# stm32103c8t6-v7.net
KiCad netlist of a schematic drawn in EAGLE
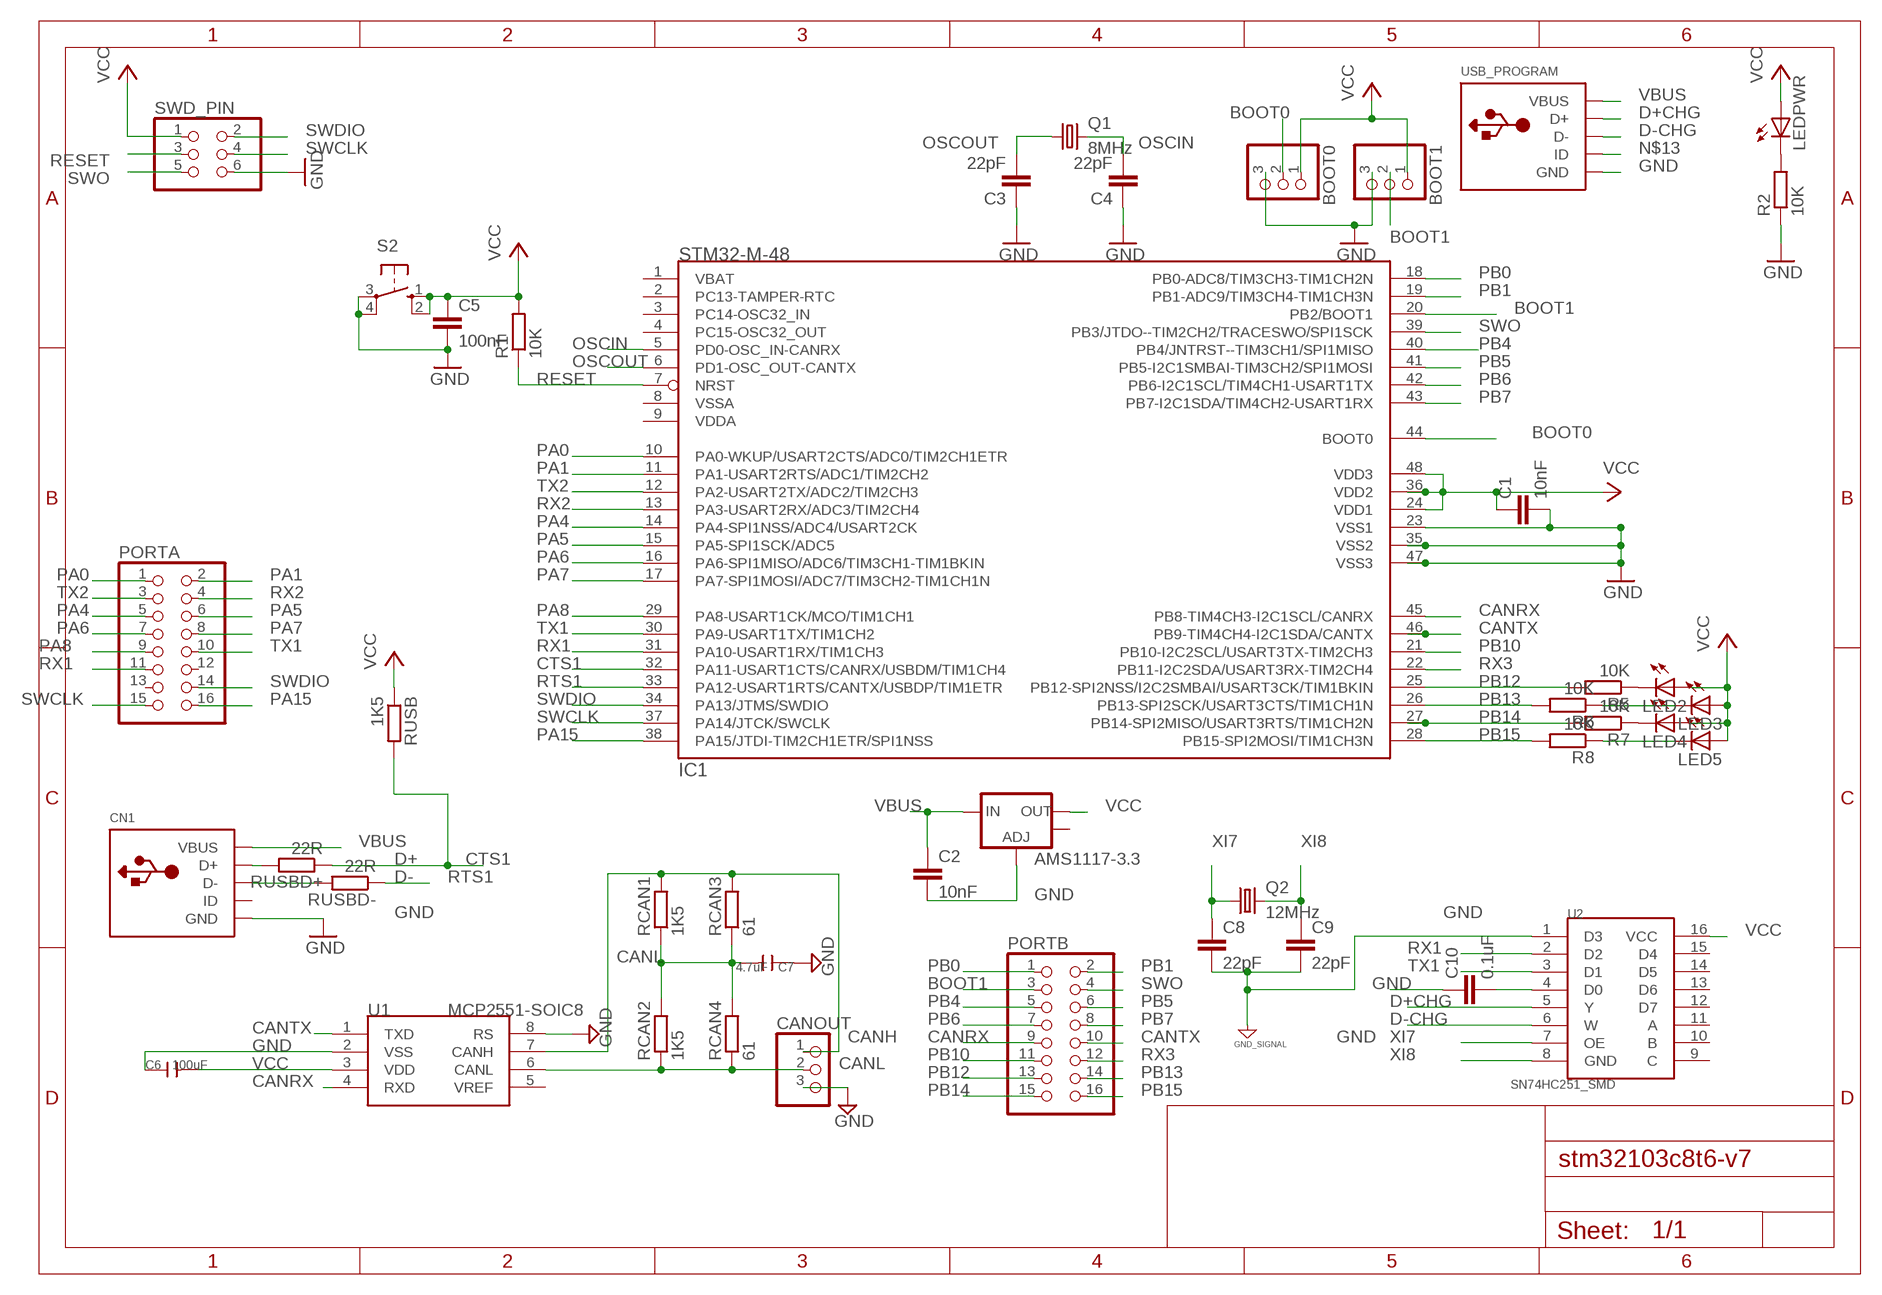
[diagram p0: schematic, sheet 1]

(export (version "E")
  (design (tool "Eeschema 10.0.6"))
  (components
    (comp (ref "AMS1117-3.3")
      (value "V_REG_LM1117SOT223")
      (footprint "eagle-import:SOT223")
      (libsource (lib "eagle-import") (part "V_REG_LM1117SOT223"))
    )
    (comp (ref "BOOT0")
      (value "PINHD-1X3")
      (footprint "eagle-import:1X03")
      (libsource (lib "eagle-import") (part "PINHD-1X3"))
    )
    (comp (ref "BOOT1")
      (value "PINHD-1X3")
      (footprint "eagle-import:1X03")
      (libsource (lib "eagle-import") (part "PINHD-1X3"))
    )
    (comp (ref "C1")
      (value "10nF")
      (footprint "eagle-import:C1210")
      (libsource (lib "eagle-import") (part "C-EUC1210"))
    )
    (comp (ref "C2")
      (value "10nF")
      (footprint "eagle-import:C1206")
      (libsource (lib "eagle-import") (part "C-EUC1206"))
    )
    (comp (ref "C3")
      (value "22pF")
      (footprint "eagle-import:C1210")
      (libsource (lib "eagle-import") (part "C-EUC1210"))
    )
    (comp (ref "C4")
      (value "22pF")
      (footprint "eagle-import:C1210")
      (libsource (lib "eagle-import") (part "C-EUC1210"))
    )
    (comp (ref "C5")
      (value "100nF")
      (footprint "eagle-import:C1206")
      (libsource (lib "eagle-import") (part "C-EUC1206"))
    )
    (comp (ref "C6")
      (value "100uF")
      (footprint "eagle-import:C1206")
      (libsource (lib "eagle-import") (part "C-1206"))
    )
    (comp (ref "C7")
      (value "4.7uF")
      (footprint "eagle-import:C1206")
      (libsource (lib "eagle-import") (part "C-1206"))
    )
    (comp (ref "C8")
      (value "22pF")
      (footprint "eagle-import:C1206")
      (libsource (lib "eagle-import") (part "C-EUC1206"))
    )
    (comp (ref "C9")
      (value "22pF")
      (footprint "eagle-import:C1206")
      (libsource (lib "eagle-import") (part "C-EUC1206"))
    )
    (comp (ref "C10")
      (value "0.1uF")
      (footprint "eagle-import:C1206")
      (libsource (lib "eagle-import") (part "C-EUC1206"))
    )
    (comp (ref "CANOUT")
      (value "PINHD-1X3")
      (footprint "eagle-import:1X03")
      (libsource (lib "eagle-import") (part "PINHD-1X3"))
    )
    (comp (ref "CN1")
      (value "USBTHM")
      (footprint "eagle-import:USB-MINIB-THM")
      (libsource (lib "eagle-import") (part "USBTHM"))
    )
    (comp (ref "IC1")
      (value "STM32-M-48")
      (footprint "eagle-import:LQFP48")
      (libsource (lib "eagle-import") (part "STM32-M-48"))
    )
    (comp (ref "LED2")
      (value "LEDSMT1206")
      (footprint "eagle-import:1206")
      (libsource (lib "eagle-import") (part "LEDSMT1206"))
    )
    (comp (ref "LED3")
      (value "LEDSMT1206")
      (footprint "eagle-import:1206")
      (libsource (lib "eagle-import") (part "LEDSMT1206"))
    )
    (comp (ref "LED4")
      (value "LEDSMT1206")
      (footprint "eagle-import:1206")
      (libsource (lib "eagle-import") (part "LEDSMT1206"))
    )
    (comp (ref "LED5")
      (value "LEDSMT1206")
      (footprint "eagle-import:1206")
      (libsource (lib "eagle-import") (part "LEDSMT1206"))
    )
    (comp (ref "LEDPWR")
      (value "LEDSMT1206")
      (footprint "eagle-import:1206")
      (libsource (lib "eagle-import") (part "LEDSMT1206"))
    )
    (comp (ref "PORTA")
      (value "PINHD-2X8")
      (footprint "eagle-import:2X08")
      (libsource (lib "eagle-import") (part "PINHD-2X8"))
    )
    (comp (ref "PORTB")
      (value "PINHD-2X8")
      (footprint "eagle-import:2X08")
      (libsource (lib "eagle-import") (part "PINHD-2X8"))
    )
    (comp (ref "Q1")
      (value "8MHz")
      (footprint "eagle-import:HC49_S")
      (libsource (lib "eagle-import") (part "CRYSTALHC49S"))
    )
    (comp (ref "Q2")
      (value "12MHz")
      (footprint "eagle-import:HC49_S")
      (libsource (lib "eagle-import") (part "CRYSTALHC49S"))
    )
    (comp (ref "R1")
      (value "10K")
      (footprint "eagle-import:R1206")
      (libsource (lib "eagle-import") (part "R-EU_R1206"))
    )
    (comp (ref "R2")
      (value "10K")
      (footprint "eagle-import:R1206")
      (libsource (lib "eagle-import") (part "R-EU_R1206"))
    )
    (comp (ref "R5")
      (value "10K")
      (footprint "eagle-import:R1206")
      (libsource (lib "eagle-import") (part "R-EU_R1206"))
    )
    (comp (ref "R6")
      (value "10K")
      (footprint "eagle-import:R1206")
      (libsource (lib "eagle-import") (part "R-EU_R1206"))
    )
    (comp (ref "R7")
      (value "10K")
      (footprint "eagle-import:R1206")
      (libsource (lib "eagle-import") (part "R-EU_R1206"))
    )
    (comp (ref "R8")
      (value "10K")
      (footprint "eagle-import:R1206")
      (libsource (lib "eagle-import") (part "R-EU_R1206"))
    )
    (comp (ref "RCAN1")
      (value "1K5")
      (footprint "eagle-import:R1206")
      (libsource (lib "eagle-import") (part "R-EU_R1206"))
    )
    (comp (ref "RCAN2")
      (value "1K5")
      (footprint "eagle-import:R1206")
      (libsource (lib "eagle-import") (part "R-EU_R1206"))
    )
    (comp (ref "RCAN3")
      (value "61")
      (footprint "eagle-import:R1206")
      (libsource (lib "eagle-import") (part "R-EU_R1206"))
    )
    (comp (ref "RCAN4")
      (value "61")
      (footprint "eagle-import:R1206")
      (libsource (lib "eagle-import") (part "R-EU_R1206"))
    )
    (comp (ref "RUSB")
      (value "1K5")
      (footprint "eagle-import:R1206")
      (libsource (lib "eagle-import") (part "R-EU_R1206"))
    )
    (comp (ref "RUSBD+")
      (value "22R")
      (footprint "eagle-import:R1206")
      (libsource (lib "eagle-import") (part "R-EU_R1206"))
    )
    (comp (ref "RUSBD-")
      (value "22R")
      (footprint "eagle-import:R1206")
      (libsource (lib "eagle-import") (part "R-EU_R1206"))
    )
    (comp (ref "S2")
      (value "10-XX")
      (footprint "eagle-import:B3F-10XX")
      (fields (field (name "MPN") "B3F-1000"))
      (libsource (lib "eagle-import") (part "10-XX"))
    )
    (comp (ref "SWD_PIN")
      (value "PINHD-2X3")
      (footprint "eagle-import:2X03")
      (libsource (lib "eagle-import") (part "PINHD-2X3"))
    )
    (comp (ref "U1")
      (value "MCP2551-SOIC8")
      (footprint "eagle-import:SOIC8-6.0")
      (libsource (lib "eagle-import") (part "MCP2551-SOIC8"))
    )
    (comp (ref "U2")
      (value "SN74HC251_SMD")
      (footprint "eagle-import:SO016")
      (libsource (lib "eagle-import") (part "SN74HC251_SMD"))
    )
    (comp (ref "USB_PROGRAM")
      (value "USBTHM")
      (footprint "eagle-import:USB-MINIB-THM")
      (libsource (lib "eagle-import") (part "USBTHM"))
    )
  )
  (nets
    (net (code "1") (name "/BOOT0") (class "Default")
      (node (ref "BOOT0") (pin "2") (pinfunction "2_2") (pintype "passive"))
      (node (ref "IC1") (pin "44") (pinfunction "BOOT0_44") (pintype "input"))
    )
    (net (code "2") (name "/BOOT1") (class "Default")
      (node (ref "BOOT1") (pin "2") (pinfunction "2_2") (pintype "passive"))
      (node (ref "IC1") (pin "20") (pinfunction "PB2/BOOT1_20") (pintype "bidirectional"))
      (node (ref "PORTB") (pin "3") (pinfunction "3_3") (pintype "passive"))
    )
    (net (code "3") (name "/CANH") (class "Default")
      (node (ref "CANOUT") (pin "1") (pinfunction "1_1") (pintype "passive"))
      (node (ref "RCAN1") (pin "2") (pinfunction "2_2") (pintype "passive"))
      (node (ref "RCAN3") (pin "2") (pinfunction "2_2") (pintype "passive"))
      (node (ref "U1") (pin "7") (pinfunction "CANH_7") (pintype "bidirectional"))
    )
    (net (code "4") (name "/CANL") (class "Default")
      (node (ref "CANOUT") (pin "2") (pinfunction "2_2") (pintype "passive"))
      (node (ref "RCAN2") (pin "1") (pinfunction "1_1") (pintype "passive"))
      (node (ref "RCAN4") (pin "1") (pinfunction "1_1") (pintype "passive"))
      (node (ref "U1") (pin "6") (pinfunction "CANL_6") (pintype "bidirectional"))
    )
    (net (code "5") (name "/CANRX") (class "Default")
      (node (ref "IC1") (pin "45") (pinfunction "PB8-TIM4CH3-I2C1SCL/CANRX_45") (pintype "bidirectional"))
      (node (ref "PORTB") (pin "9") (pinfunction "9_9") (pintype "passive"))
      (node (ref "U1") (pin "4") (pinfunction "RXD_4") (pintype "bidirectional"))
    )
    (net (code "6") (name "/CANTX") (class "Default")
      (node (ref "IC1") (pin "46") (pinfunction "PB9-TIM4CH4-I2C1SDA/CANTX_46") (pintype "bidirectional"))
      (node (ref "PORTB") (pin "10") (pinfunction "10_10") (pintype "passive"))
      (node (ref "U1") (pin "1") (pinfunction "TXD_1") (pintype "bidirectional"))
    )
    (net (code "7") (name "/CTS1") (class "Default")
      (node (ref "IC1") (pin "32") (pinfunction "PA11-USART1CTS/CANRX/USBDM/TIM1CH4_32") (pintype "bidirectional"))
      (node (ref "RUSB") (pin "2") (pinfunction "2_2") (pintype "passive"))
      (node (ref "RUSBD+") (pin "1") (pinfunction "1_1") (pintype "passive"))
    )
    (net (code "8") (name "/D+") (class "Default")
      (node (ref "CN1") (pin "D+") (pinfunction "D+_D+") (pintype "bidirectional"))
      (node (ref "RUSBD+") (pin "2") (pinfunction "2_2") (pintype "passive"))
    )
    (net (code "9") (name "/D+CHG") (class "Default")
      (node (ref "U2") (pin "5") (pinfunction "Y_5") (pintype "bidirectional"))
      (node (ref "USB_PROGRAM") (pin "D+") (pinfunction "D+_D+") (pintype "bidirectional"))
    )
    (net (code "10") (name "/D-") (class "Default")
      (node (ref "CN1") (pin "D-") (pinfunction "D-_D-") (pintype "bidirectional"))
      (node (ref "RUSBD-") (pin "2") (pinfunction "2_2") (pintype "passive"))
    )
    (net (code "11") (name "/D-CHG") (class "Default")
      (node (ref "U2") (pin "6") (pinfunction "W_6") (pintype "bidirectional"))
      (node (ref "USB_PROGRAM") (pin "D-") (pinfunction "D-_D-") (pintype "bidirectional"))
    )
    (net (code "12") (name "/N$13") (class "Default")
      (node (ref "USB_PROGRAM") (pin "ID") (pinfunction "ID_ID") (pintype "bidirectional"))
    )
    (net (code "13") (name "/OSCIN") (class "Default")
      (node (ref "C4") (pin "2") (pinfunction "2_2") (pintype "passive"))
      (node (ref "IC1") (pin "5") (pinfunction "PD0-OSC_IN-CANRX_5") (pintype "input"))
      (node (ref "Q1") (pin "2") (pinfunction "2_2") (pintype "passive"))
    )
    (net (code "14") (name "/OSCOUT") (class "Default")
      (node (ref "C3") (pin "2") (pinfunction "2_2") (pintype "passive"))
      (node (ref "IC1") (pin "6") (pinfunction "PD1-OSC_OUT-CANTX_6") (pintype "output"))
      (node (ref "Q1") (pin "1") (pinfunction "1_1") (pintype "passive"))
    )
    (net (code "15") (name "/PA0") (class "Default")
      (node (ref "IC1") (pin "10") (pinfunction "PA0-WKUP/USART2CTS/ADC0/TIM2CH1ETR_10") (pintype "bidirectional"))
      (node (ref "PORTA") (pin "1") (pinfunction "1_1") (pintype "passive"))
    )
    (net (code "16") (name "/PA1") (class "Default")
      (node (ref "IC1") (pin "11") (pinfunction "PA1-USART2RTS/ADC1/TIM2CH2_11") (pintype "bidirectional"))
      (node (ref "PORTA") (pin "2") (pinfunction "2_2") (pintype "passive"))
    )
    (net (code "17") (name "/PA4") (class "Default")
      (node (ref "IC1") (pin "14") (pinfunction "PA4-SPI1NSS/ADC4/USART2CK_14") (pintype "bidirectional"))
      (node (ref "PORTA") (pin "5") (pinfunction "5_5") (pintype "passive"))
    )
    (net (code "18") (name "/PA5") (class "Default")
      (node (ref "IC1") (pin "15") (pinfunction "PA5-SPI1SCK/ADC5_15") (pintype "bidirectional"))
      (node (ref "PORTA") (pin "6") (pinfunction "6_6") (pintype "passive"))
    )
    (net (code "19") (name "/PA6") (class "Default")
      (node (ref "IC1") (pin "16") (pinfunction "PA6-SPI1MISO/ADC6/TIM3CH1-TIM1BKIN_16") (pintype "bidirectional"))
      (node (ref "PORTA") (pin "7") (pinfunction "7_7") (pintype "passive"))
    )
    (net (code "20") (name "/PA7") (class "Default")
      (node (ref "IC1") (pin "17") (pinfunction "PA7-SPI1MOSI/ADC7/TIM3CH2-TIM1CH1N_17") (pintype "bidirectional"))
      (node (ref "PORTA") (pin "8") (pinfunction "8_8") (pintype "passive"))
    )
    (net (code "21") (name "/PA8") (class "Default")
      (node (ref "IC1") (pin "29") (pinfunction "PA8-USART1CK/MCO/TIM1CH1_29") (pintype "bidirectional"))
      (node (ref "PORTA") (pin "9") (pinfunction "9_9") (pintype "passive"))
    )
    (net (code "22") (name "/PA15") (class "Default")
      (node (ref "IC1") (pin "38") (pinfunction "PA15/JTDI-TIM2CH1ETR/SPI1NSS_38") (pintype "bidirectional"))
      (node (ref "PORTA") (pin "16") (pinfunction "16_16") (pintype "passive"))
    )
    (net (code "23") (name "/PB0") (class "Default")
      (node (ref "IC1") (pin "18") (pinfunction "PB0-ADC8/TIM3CH3-TIM1CH2N_18") (pintype "bidirectional"))
      (node (ref "PORTB") (pin "1") (pinfunction "1_1") (pintype "passive"))
    )
    (net (code "24") (name "/PB1") (class "Default")
      (node (ref "IC1") (pin "19") (pinfunction "PB1-ADC9/TIM3CH4-TIM1CH3N_19") (pintype "bidirectional"))
      (node (ref "PORTB") (pin "2") (pinfunction "2_2") (pintype "passive"))
    )
    (net (code "25") (name "/PB4") (class "Default")
      (node (ref "IC1") (pin "40") (pinfunction "PB4/JNTRST--TIM3CH1/SPI1MISO_40") (pintype "bidirectional"))
      (node (ref "PORTB") (pin "5") (pinfunction "5_5") (pintype "passive"))
    )
    (net (code "26") (name "/PB5") (class "Default")
      (node (ref "IC1") (pin "41") (pinfunction "PB5-I2C1SMBAI-TIM3CH2/SPI1MOSI_41") (pintype "bidirectional"))
      (node (ref "PORTB") (pin "6") (pinfunction "6_6") (pintype "passive"))
    )
    (net (code "27") (name "/PB6") (class "Default")
      (node (ref "IC1") (pin "42") (pinfunction "PB6-I2C1SCL/TIM4CH1-USART1TX_42") (pintype "bidirectional"))
      (node (ref "PORTB") (pin "7") (pinfunction "7_7") (pintype "passive"))
    )
    (net (code "28") (name "/PB7") (class "Default")
      (node (ref "IC1") (pin "43") (pinfunction "PB7-I2C1SDA/TIM4CH2-USART1RX_43") (pintype "bidirectional"))
      (node (ref "PORTB") (pin "8") (pinfunction "8_8") (pintype "passive"))
    )
    (net (code "29") (name "/PB10") (class "Default")
      (node (ref "IC1") (pin "21") (pinfunction "PB10-I2C2SCL/USART3TX-TIM2CH3_21") (pintype "bidirectional"))
      (node (ref "PORTB") (pin "11") (pinfunction "11_11") (pintype "passive"))
    )
    (net (code "30") (name "/PB12") (class "Default")
      (node (ref "IC1") (pin "25") (pinfunction "PB12-SPI2NSS/I2C2SMBAI/USART3CK/TIM1BKIN_25") (pintype "bidirectional"))
      (node (ref "PORTB") (pin "13") (pinfunction "13_13") (pintype "passive"))
      (node (ref "R5") (pin "2") (pinfunction "2_2") (pintype "passive"))
    )
    (net (code "31") (name "/PB13") (class "Default")
      (node (ref "IC1") (pin "26") (pinfunction "PB13-SPI2SCK/USART3CTS/TIM1CH1N_26") (pintype "bidirectional"))
      (node (ref "PORTB") (pin "14") (pinfunction "14_14") (pintype "passive"))
      (node (ref "R6") (pin "2") (pinfunction "2_2") (pintype "passive"))
    )
    (net (code "32") (name "/PB14") (class "Default")
      (node (ref "IC1") (pin "27") (pinfunction "PB14-SPI2MISO/USART3RTS/TIM1CH2N_27") (pintype "bidirectional"))
      (node (ref "PORTB") (pin "15") (pinfunction "15_15") (pintype "passive"))
      (node (ref "R7") (pin "2") (pinfunction "2_2") (pintype "passive"))
    )
    (net (code "33") (name "/PB15") (class "Default")
      (node (ref "IC1") (pin "28") (pinfunction "PB15-SPI2MOSI/TIM1CH3N_28") (pintype "bidirectional"))
      (node (ref "PORTB") (pin "16") (pinfunction "16_16") (pintype "passive"))
      (node (ref "R8") (pin "2") (pinfunction "2_2") (pintype "passive"))
    )
    (net (code "34") (name "/RESET") (class "Default")
      (node (ref "IC1") (pin "7") (pinfunction "NRST_7") (pintype "bidirectional"))
      (node (ref "R1") (pin "1") (pinfunction "1_1") (pintype "passive"))
      (node (ref "SWD_PIN") (pin "3") (pinfunction "3_3") (pintype "passive"))
    )
    (net (code "35") (name "/RTS1") (class "Default")
      (node (ref "IC1") (pin "33") (pinfunction "PA12-USART1RTS/CANTX/USBDP/TIM1ETR_33") (pintype "bidirectional"))
      (node (ref "RUSBD-") (pin "1") (pinfunction "1_1") (pintype "passive"))
    )
    (net (code "36") (name "/RX1") (class "Default")
      (node (ref "IC1") (pin "31") (pinfunction "PA10-USART1RX/TIM1CH3_31") (pintype "bidirectional"))
      (node (ref "PORTA") (pin "11") (pinfunction "11_11") (pintype "passive"))
      (node (ref "U2") (pin "2") (pinfunction "D2_2") (pintype "bidirectional"))
    )
    (net (code "37") (name "/RX2") (class "Default")
      (node (ref "IC1") (pin "13") (pinfunction "PA3-USART2RX/ADC3/TIM2CH4_13") (pintype "bidirectional"))
      (node (ref "PORTA") (pin "4") (pinfunction "4_4") (pintype "passive"))
    )
    (net (code "38") (name "/RX3") (class "Default")
      (node (ref "IC1") (pin "22") (pinfunction "PB11-I2C2SDA/USART3RX-TIM2CH4_22") (pintype "bidirectional"))
      (node (ref "PORTB") (pin "12") (pinfunction "12_12") (pintype "passive"))
    )
    (net (code "39") (name "/SWCLK") (class "Default")
      (node (ref "IC1") (pin "37") (pinfunction "PA14/JTCK/SWCLK_37") (pintype "bidirectional"))
      (node (ref "PORTA") (pin "15") (pinfunction "15_15") (pintype "passive"))
      (node (ref "SWD_PIN") (pin "4") (pinfunction "4_4") (pintype "passive"))
    )
    (net (code "40") (name "/SWDIO") (class "Default")
      (node (ref "IC1") (pin "34") (pinfunction "PA13/JTMS/SWDIO_34") (pintype "bidirectional"))
      (node (ref "PORTA") (pin "14") (pinfunction "14_14") (pintype "passive"))
      (node (ref "SWD_PIN") (pin "2") (pinfunction "2_2") (pintype "passive"))
    )
    (net (code "41") (name "/SWO") (class "Default")
      (node (ref "IC1") (pin "39") (pinfunction "PB3/JTDO--TIM2CH2/TRACESWO/SPI1SCK_39") (pintype "bidirectional"))
      (node (ref "PORTB") (pin "4") (pinfunction "4_4") (pintype "passive"))
      (node (ref "SWD_PIN") (pin "5") (pinfunction "5_5") (pintype "passive"))
    )
    (net (code "42") (name "/TX1") (class "Default")
      (node (ref "IC1") (pin "30") (pinfunction "PA9-USART1TX/TIM1CH2_30") (pintype "bidirectional"))
      (node (ref "PORTA") (pin "10") (pinfunction "10_10") (pintype "passive"))
      (node (ref "U2") (pin "3") (pinfunction "D1_3") (pintype "bidirectional"))
    )
    (net (code "43") (name "/TX2") (class "Default")
      (node (ref "IC1") (pin "12") (pinfunction "PA2-USART2TX/ADC2/TIM2CH3_12") (pintype "bidirectional"))
      (node (ref "PORTA") (pin "3") (pinfunction "3_3") (pintype "passive"))
    )
    (net (code "44") (name "/VBAT") (class "Default")
      (node (ref "IC1") (pin "1") (pinfunction "VBAT_1") (pintype "power_in"))
    )
    (net (code "45") (name "/VBUS") (class "Default")
      (node (ref "AMS1117-3.3") (pin "3") (pinfunction "IN_3") (pintype "input"))
      (node (ref "C2") (pin "1") (pinfunction "1_1") (pintype "passive"))
      (node (ref "CN1") (pin "VBUS") (pinfunction "VBUS_VBUS") (pintype "power_in"))
      (node (ref "USB_PROGRAM") (pin "VBUS") (pinfunction "VBUS_VBUS") (pintype "power_in"))
    )
    (net (code "46") (name "/VDDA") (class "Default")
      (node (ref "IC1") (pin "9") (pinfunction "VDDA_9") (pintype "power_in"))
    )
    (net (code "47") (name "/VSSA") (class "Default")
      (node (ref "IC1") (pin "8") (pinfunction "VSSA_8") (pintype "power_in"))
    )
    (net (code "48") (name "/XI7") (class "Default")
      (node (ref "C8") (pin "1") (pinfunction "1_1") (pintype "passive"))
      (node (ref "Q2") (pin "1") (pinfunction "1_1") (pintype "passive"))
      (node (ref "U2") (pin "7") (pinfunction "OE_7") (pintype "bidirectional"))
    )
    (net (code "49") (name "/XI8") (class "Default")
      (node (ref "C9") (pin "1") (pinfunction "1_1") (pintype "passive"))
      (node (ref "Q2") (pin "2") (pinfunction "2_2") (pintype "passive"))
      (node (ref "U2") (pin "8") (pinfunction "GND_8") (pintype "bidirectional"))
    )
    (net (code "50") (name "GND") (class "Default")
      (node (ref "AMS1117-3.3") (pin "1") (pinfunction "ADJ_1") (pintype "input"))
      (node (ref "BOOT0") (pin "3") (pinfunction "3_3") (pintype "passive"))
      (node (ref "BOOT1") (pin "3") (pinfunction "3_3") (pintype "passive"))
      (node (ref "C1") (pin "2") (pinfunction "2_2") (pintype "passive"))
      (node (ref "C10") (pin "1") (pinfunction "1_1") (pintype "passive"))
      (node (ref "C2") (pin "2") (pinfunction "2_2") (pintype "passive"))
      (node (ref "C3") (pin "1") (pinfunction "1_1") (pintype "passive"))
      (node (ref "C4") (pin "1") (pinfunction "1_1") (pintype "passive"))
      (node (ref "C5") (pin "2") (pinfunction "2_2") (pintype "passive"))
      (node (ref "C6") (pin "1") (pinfunction "1_1") (pintype "passive"))
      (node (ref "C7") (pin "1") (pinfunction "1_1") (pintype "passive"))
      (node (ref "C8") (pin "2") (pinfunction "2_2") (pintype "passive"))
      (node (ref "C9") (pin "2") (pinfunction "2_2") (pintype "passive"))
      (node (ref "CANOUT") (pin "3") (pinfunction "3_3") (pintype "passive"))
      (node (ref "CN1") (pin "GND") (pinfunction "GND_GND") (pintype "power_in"))
      (node (ref "IC1") (pin "23") (pinfunction "VSS1_23") (pintype "power_in"))
      (node (ref "IC1") (pin "35") (pinfunction "VSS2_35") (pintype "power_in"))
      (node (ref "IC1") (pin "47") (pinfunction "VSS3_47") (pintype "power_in"))
      (node (ref "R2") (pin "1") (pinfunction "1_1") (pintype "passive"))
      (node (ref "S2") (pin "3") (pinfunction "P_3") (pintype "passive"))
      (node (ref "S2") (pin "4") (pinfunction "P1_4") (pintype "passive"))
      (node (ref "SWD_PIN") (pin "6") (pinfunction "6_6") (pintype "passive"))
      (node (ref "U1") (pin "2") (pinfunction "VSS_2") (pintype "bidirectional"))
      (node (ref "U1") (pin "8") (pinfunction "RS_8") (pintype "bidirectional"))
      (node (ref "U2") (pin "1") (pinfunction "D3_1") (pintype "bidirectional"))
      (node (ref "USB_PROGRAM") (pin "GND") (pinfunction "GND_GND") (pintype "power_in"))
    )
    (net (code "51") (name "Net-(C7-Pad2)") (class "Default")
      (node (ref "C7") (pin "2") (pinfunction "2_2") (pintype "passive"))
      (node (ref "RCAN1") (pin "1") (pinfunction "1_1") (pintype "passive"))
      (node (ref "RCAN2") (pin "2") (pinfunction "2_2") (pintype "passive"))
      (node (ref "RCAN3") (pin "1") (pinfunction "1_1") (pintype "passive"))
      (node (ref "RCAN4") (pin "2") (pinfunction "2_2") (pintype "passive"))
    )
    (net (code "52") (name "Net-(LED2-PadC)") (class "Default")
      (node (ref "LED2") (pin "C") (pinfunction "C_C") (pintype "passive"))
      (node (ref "R5") (pin "1") (pinfunction "1_1") (pintype "passive"))
    )
    (net (code "53") (name "Net-(LED3-PadC)") (class "Default")
      (node (ref "LED3") (pin "C") (pinfunction "C_C") (pintype "passive"))
      (node (ref "R6") (pin "1") (pinfunction "1_1") (pintype "passive"))
    )
    (net (code "54") (name "Net-(LED4-PadC)") (class "Default")
      (node (ref "LED4") (pin "C") (pinfunction "C_C") (pintype "passive"))
      (node (ref "R7") (pin "1") (pinfunction "1_1") (pintype "passive"))
    )
    (net (code "55") (name "Net-(LED5-PadC)") (class "Default")
      (node (ref "LED5") (pin "C") (pinfunction "C_C") (pintype "passive"))
      (node (ref "R8") (pin "1") (pinfunction "1_1") (pintype "passive"))
    )
    (net (code "56") (name "Net-(LEDPWR-PadC)") (class "Default")
      (node (ref "LEDPWR") (pin "C") (pinfunction "C_C") (pintype "passive"))
      (node (ref "R2") (pin "2") (pinfunction "2_2") (pintype "passive"))
    )
    (net (code "57") (name "Net-(U2-D0)") (class "Default")
      (node (ref "C10") (pin "2") (pinfunction "2_2") (pintype "passive"))
      (node (ref "U2") (pin "4") (pinfunction "D0_4") (pintype "bidirectional"))
    )
    (net (code "58") (name "VCC") (class "Default")
      (node (ref "AMS1117-3.3") (pin "2") (pinfunction "OUT_2") (pintype "output"))
      (node (ref "BOOT0") (pin "1") (pinfunction "1_1") (pintype "passive"))
      (node (ref "BOOT1") (pin "1") (pinfunction "1_1") (pintype "passive"))
      (node (ref "C1") (pin "1") (pinfunction "1_1") (pintype "passive"))
      (node (ref "C5") (pin "1") (pinfunction "1_1") (pintype "passive"))
      (node (ref "C6") (pin "2") (pinfunction "2_2") (pintype "passive"))
      (node (ref "IC1") (pin "24") (pinfunction "VDD1_24") (pintype "power_in"))
      (node (ref "IC1") (pin "36") (pinfunction "VDD2_36") (pintype "power_in"))
      (node (ref "IC1") (pin "48") (pinfunction "VDD3_48") (pintype "power_in"))
      (node (ref "LED2") (pin "A") (pinfunction "A_A") (pintype "passive"))
      (node (ref "LED3") (pin "A") (pinfunction "A_A") (pintype "passive"))
      (node (ref "LED4") (pin "A") (pinfunction "A_A") (pintype "passive"))
      (node (ref "LED5") (pin "A") (pinfunction "A_A") (pintype "passive"))
      (node (ref "LEDPWR") (pin "A") (pinfunction "A_A") (pintype "passive"))
      (node (ref "R1") (pin "2") (pinfunction "2_2") (pintype "passive"))
      (node (ref "RUSB") (pin "1") (pinfunction "1_1") (pintype "passive"))
      (node (ref "S2") (pin "1") (pinfunction "S_1") (pintype "passive"))
      (node (ref "S2") (pin "2") (pinfunction "S1_2") (pintype "passive"))
      (node (ref "SWD_PIN") (pin "1") (pinfunction "1_1") (pintype "passive"))
      (node (ref "U1") (pin "3") (pinfunction "VDD_3") (pintype "bidirectional"))
      (node (ref "U2") (pin "16") (pinfunction "VCC_16") (pintype "bidirectional"))
    )
    (net (code "59") (name "unconnected-(AMS1117-3.3-OUT-Pad4)") (class "Default")
      (node (ref "AMS1117-3.3") (pin "4") (pinfunction "OUT_4") (pintype "output"))
    )
    (net (code "60") (name "unconnected-(CN1-PadID)") (class "Default")
      (node (ref "CN1") (pin "ID") (pinfunction "ID_ID") (pintype "bidirectional"))
    )
    (net (code "61") (name "unconnected-(IC1-PC13-TAMPER-RTC-Pad2)") (class "Default")
      (node (ref "IC1") (pin "2") (pinfunction "PC13-TAMPER-RTC_2") (pintype "bidirectional"))
    )
    (net (code "62") (name "unconnected-(IC1-PC14-OSC32_IN-Pad3)") (class "Default")
      (node (ref "IC1") (pin "3") (pinfunction "PC14-OSC32_IN_3") (pintype "bidirectional"))
    )
    (net (code "63") (name "unconnected-(IC1-PC15-OSC32_OUT-Pad4)") (class "Default")
      (node (ref "IC1") (pin "4") (pinfunction "PC15-OSC32_OUT_4") (pintype "bidirectional"))
    )
    (net (code "64") (name "unconnected-(PORTA-Pad12)") (class "Default")
      (node (ref "PORTA") (pin "12") (pinfunction "12_12") (pintype "passive"))
    )
    (net (code "65") (name "unconnected-(PORTA-Pad13)") (class "Default")
      (node (ref "PORTA") (pin "13") (pinfunction "13_13") (pintype "passive"))
    )
    (net (code "66") (name "unconnected-(U1-VREF-Pad5)") (class "Default")
      (node (ref "U1") (pin "5") (pinfunction "VREF_5") (pintype "bidirectional"))
    )
    (net (code "67") (name "unconnected-(U2-A-Pad11)") (class "Default")
      (node (ref "U2") (pin "11") (pinfunction "A_11") (pintype "bidirectional"))
    )
    (net (code "68") (name "unconnected-(U2-B-Pad10)") (class "Default")
      (node (ref "U2") (pin "10") (pinfunction "B_10") (pintype "bidirectional"))
    )
    (net (code "69") (name "unconnected-(U2-C-Pad9)") (class "Default")
      (node (ref "U2") (pin "9") (pinfunction "C_9") (pintype "bidirectional"))
    )
    (net (code "70") (name "unconnected-(U2-D4-Pad15)") (class "Default")
      (node (ref "U2") (pin "15") (pinfunction "D4_15") (pintype "bidirectional"))
    )
    (net (code "71") (name "unconnected-(U2-D5-Pad14)") (class "Default")
      (node (ref "U2") (pin "14") (pinfunction "D5_14") (pintype "bidirectional"))
    )
    (net (code "72") (name "unconnected-(U2-D6-Pad13)") (class "Default")
      (node (ref "U2") (pin "13") (pinfunction "D6_13") (pintype "bidirectional"))
    )
    (net (code "73") (name "unconnected-(U2-D7-Pad12)") (class "Default")
      (node (ref "U2") (pin "12") (pinfunction "D7_12") (pintype "bidirectional"))
    )
  )
)
